# GTM_MCU.net
KiCad netlist of a schematic drawn in Altium Designer
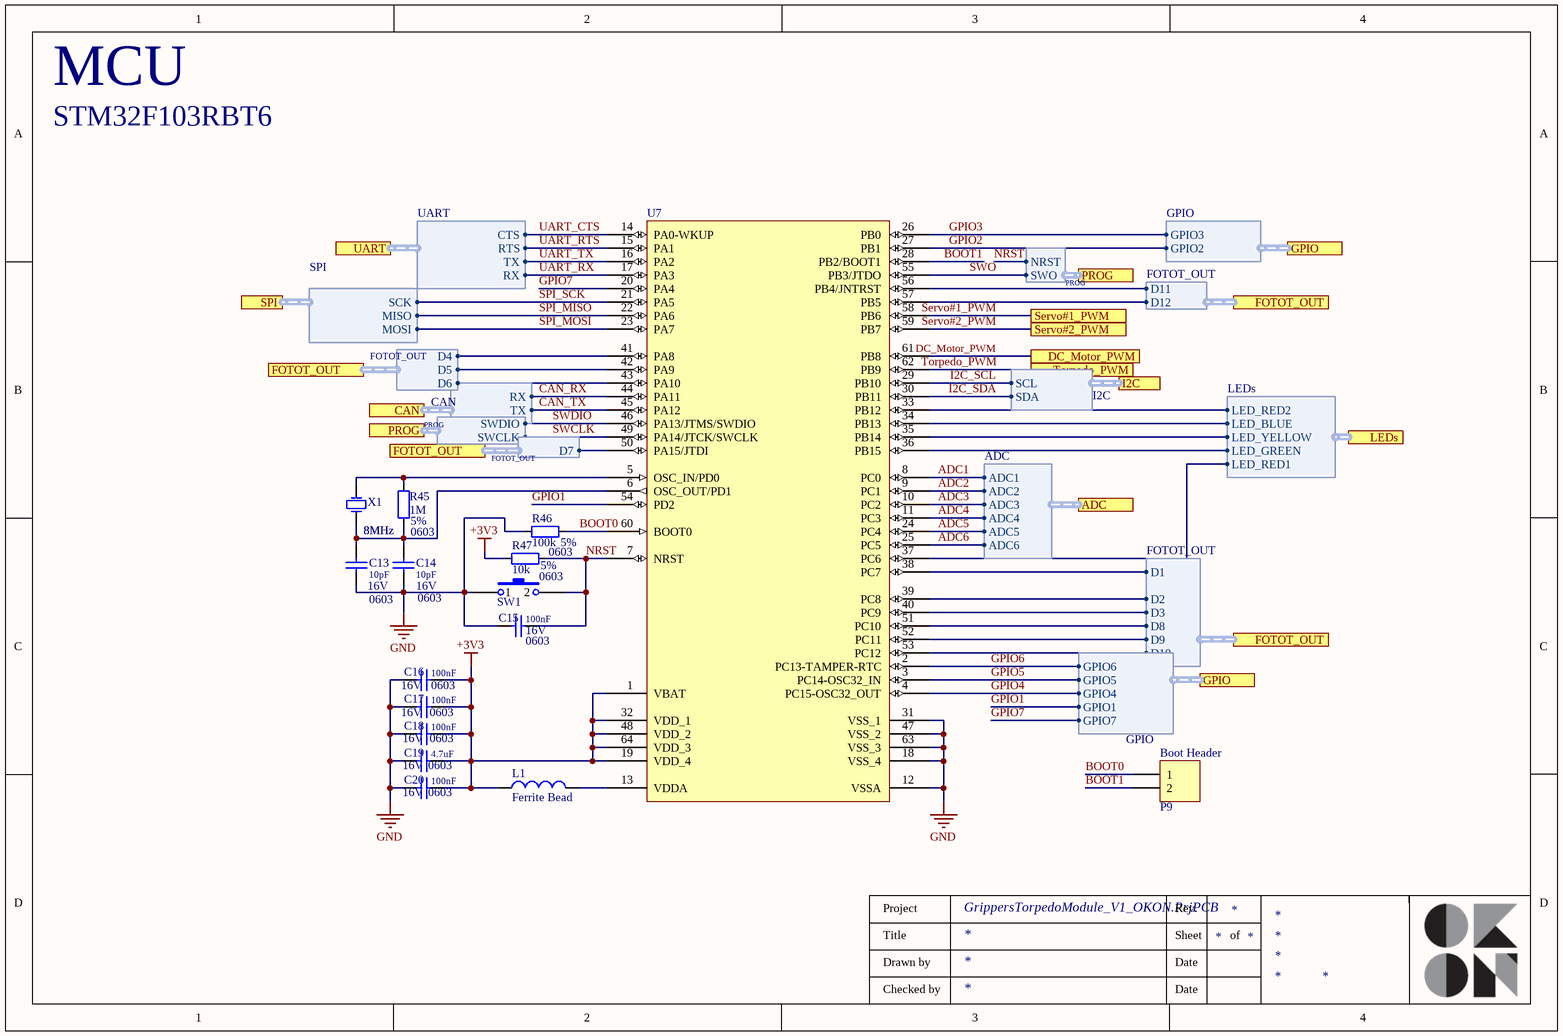
[diagram p0: GTM_MCU.SchDoc]

(export (version "E")
  (design (tool "Eeschema 10.0.6"))
  (components
    (comp (ref "C13")
      (value "10pF")
      (footprint "0603_CAP")
      (description "Ceramic capacitor")
      (fields (field (name "CAPACITY") "16V") (field (name "PACKAGE") "0603") (field (name "Comment") "Cap"))
      (libsource (lib "Library_Altium_KNR") (part "Cap"))
    )
    (comp (ref "C14")
      (value "10pF")
      (footprint "0603_CAP")
      (description "Ceramic capacitor")
      (fields (field (name "CAPACITY") "16V") (field (name "PACKAGE") "0603") (field (name "Comment") "Cap"))
      (libsource (lib "Library_Altium_KNR") (part "Cap"))
    )
    (comp (ref "C15")
      (value "100nF")
      (footprint "0603_CAP")
      (description "Ceramic capacitor")
      (fields (field (name "CAPACITY") "16V") (field (name "PACKAGE") "0603") (field (name "Comment") "Cap"))
      (libsource (lib "Library_Altium_KNR") (part "Cap"))
    )
    (comp (ref "C16")
      (value "100nF")
      (footprint "0603_CAP")
      (description "Ceramic capacitor")
      (fields (field (name "CAPACITY") "16V") (field (name "PACKAGE") "0603") (field (name "Comment") "Cap"))
      (libsource (lib "Library_Altium_KNR") (part "Cap"))
    )
    (comp (ref "C17")
      (value "100nF")
      (footprint "0603_CAP")
      (description "Ceramic capacitor")
      (fields (field (name "CAPACITY") "16V") (field (name "PACKAGE") "0603") (field (name "Comment") "Cap"))
      (libsource (lib "Library_Altium_KNR") (part "Cap"))
    )
    (comp (ref "C18")
      (value "100nF")
      (footprint "0603_CAP")
      (description "Ceramic capacitor")
      (fields (field (name "CAPACITY") "16V") (field (name "PACKAGE") "0603") (field (name "Comment") "Cap"))
      (libsource (lib "Library_Altium_KNR") (part "Cap"))
    )
    (comp (ref "C19")
      (value "4.7uF")
      (footprint "0603_CAP")
      (description "Ceramic capacitor")
      (fields (field (name "CAPACITY") "16V") (field (name "PACKAGE") "0603") (field (name "Comment") "Cap"))
      (libsource (lib "Library_Altium_KNR") (part "Cap"))
    )
    (comp (ref "C20")
      (value "100nF")
      (footprint "0603_CAP")
      (description "Ceramic capacitor")
      (fields (field (name "CAPACITY") "16V") (field (name "PACKAGE") "0603") (field (name "Comment") "Cap"))
      (libsource (lib "Library_Altium_KNR") (part "Cap"))
    )
    (comp (ref "L1")
      (value "Ferrite Bead")
      (footprint "DO5040")
      (description "DO5040H-103")
      (fields (field (name "PUBLISHER") "Altium Limited"))
      (libsource (lib "Library_Altium_KNR") (part "Inductor"))
    )
    (comp (ref "P9")
      (value "Boot Header")
      (footprint "HDR1X2")
      (description "Header, 2-Pin")
      (fields (field (name "PUBLISHER") "Altium Limited"))
      (libsource (lib "Library_Altium_KNR") (part "HDR1X2"))
    )
    (comp (ref "R45")
      (value "1M")
      (footprint "0603")
      (description "Resistior")
      (fields (field (name "TOLERANCE") "5%") (field (name "PACKAGE") "0603"))
      (libsource (lib "") (part "RES_1"))
    )
    (comp (ref "R46")
      (value "100k")
      (footprint "0603")
      (description "Resistior")
      (fields (field (name "TOLERANCE") "5%") (field (name "PACKAGE") "0603"))
      (libsource (lib "Library_Altium_KNR") (part "RES"))
    )
    (comp (ref "R47")
      (value "10k")
      (footprint "0603")
      (description "Resistior")
      (fields (field (name "TOLERANCE") "5%") (field (name "PACKAGE") "0603"))
      (libsource (lib "Library_Altium_KNR") (part "RES"))
    )
    (comp (ref "SW1")
      (value "Micro_Switch")
      (footprint "Tact 34N-F")
      (description "Switch")
      (fields (field (name "PUBLISHER") "Altium Limited"))
      (libsource (lib "Library_Altium_KNR") (part "Micro_Switch"))
    )
    (comp (ref "U7")
      (value "STM32F103RBT6")
      (footprint "LQFP64_L")
      (description "STM32 ARM-based 32-bit")
      (fields (field (name "PUBLISHER") "Altium Limited"))
      (libsource (lib "Library_Altium_KNR") (part "STM32F103RBT6"))
    )
    (comp (ref "X1")
      (value "8MHz")
      (footprint "HC49/4H_SMX")
      (description "Oscillator")
      (fields (field (name "ALTIUM_VALUE") "8MHz"))
      (libsource (lib "Library_Altium_KNR") (part "XTAL"))
    )
  )
  (nets
    (net (code "10") (name "+3V3") (class "Default")
      (node (ref "C16") (pin "2") (pinfunction "2_2") (pintype "passive"))
      (node (ref "C17") (pin "2") (pinfunction "2_2") (pintype "passive"))
      (node (ref "C18") (pin "2") (pinfunction "2_2") (pintype "passive"))
      (node (ref "C19") (pin "2") (pinfunction "2_2") (pintype "passive"))
      (node (ref "C20") (pin "2") (pinfunction "2_2") (pintype "passive"))
      (node (ref "L1") (pin "1") (pinfunction "1_1") (pintype "passive"))
      (node (ref "R47") (pin "2") (pinfunction "2_2") (pintype "passive"))
      (node (ref "U7") (pin "1") (pinfunction "VBAT_1") (pintype "power_in"))
      (node (ref "U7") (pin "19") (pinfunction "VDD_4_19") (pintype "power_in"))
      (node (ref "U7") (pin "32") (pinfunction "VDD_1_32") (pintype "power_in"))
      (node (ref "U7") (pin "48") (pinfunction "VDD_2_48") (pintype "power_in"))
      (node (ref "U7") (pin "64") (pinfunction "VDD_3_64") (pintype "power_in"))
    )
    (net (code "11") (name "/ADC1") (class "Default")
      (node (ref "U7") (pin "8") (pinfunction "PC0_8") (pintype "bidirectional"))
    )
    (net (code "12") (name "/ADC2") (class "Default")
      (node (ref "U7") (pin "9") (pinfunction "PC1_9") (pintype "bidirectional"))
    )
    (net (code "13") (name "/ADC3") (class "Default")
      (node (ref "U7") (pin "10") (pinfunction "PC2_10") (pintype "bidirectional"))
    )
    (net (code "14") (name "/ADC4") (class "Default")
      (node (ref "U7") (pin "11") (pinfunction "PC3_11") (pintype "bidirectional"))
    )
    (net (code "15") (name "/ADC5") (class "Default")
      (node (ref "U7") (pin "24") (pinfunction "PC4_24") (pintype "bidirectional"))
    )
    (net (code "16") (name "/ADC6") (class "Default")
      (node (ref "U7") (pin "25") (pinfunction "PC5_25") (pintype "bidirectional"))
    )
    (net (code "17") (name "/BOOT0") (class "Default")
      (node (ref "P9") (pin "1") (pinfunction "1_1") (pintype "passive"))
      (node (ref "R46") (pin "1") (pinfunction "1_1") (pintype "passive"))
      (node (ref "U7") (pin "60") (pinfunction "BOOT0_60") (pintype "input"))
    )
    (net (code "18") (name "/BOOT1") (class "Default")
      (node (ref "P9") (pin "2") (pinfunction "2_2") (pintype "passive"))
      (node (ref "U7") (pin "28") (pinfunction "PB2/BOOT1_28") (pintype "bidirectional"))
    )
    (net (code "19") (name "/CAN_RX") (class "Default")
      (node (ref "U7") (pin "44") (pinfunction "PA11_44") (pintype "bidirectional"))
    )
    (net (code "20") (name "/CAN_TX") (class "Default")
      (node (ref "U7") (pin "45") (pinfunction "PA12_45") (pintype "bidirectional"))
    )
    (net (code "21") (name "/D1") (class "Default")
      (node (ref "U7") (pin "38") (pinfunction "PC7_38") (pintype "bidirectional"))
    )
    (net (code "22") (name "/D2") (class "Default")
      (node (ref "U7") (pin "39") (pinfunction "PC8_39") (pintype "bidirectional"))
    )
    (net (code "23") (name "/D3") (class "Default")
      (node (ref "U7") (pin "40") (pinfunction "PC9_40") (pintype "bidirectional"))
    )
    (net (code "24") (name "/D4") (class "Default")
      (node (ref "U7") (pin "41") (pinfunction "PA8_41") (pintype "bidirectional"))
    )
    (net (code "25") (name "/D5") (class "Default")
      (node (ref "U7") (pin "42") (pinfunction "PA9_42") (pintype "bidirectional"))
    )
    (net (code "26") (name "/D6") (class "Default")
      (node (ref "U7") (pin "43") (pinfunction "PA10_43") (pintype "bidirectional"))
    )
    (net (code "27") (name "/D7") (class "Default")
      (node (ref "U7") (pin "50") (pinfunction "PA15/JTDI_50") (pintype "bidirectional"))
    )
    (net (code "28") (name "/D8") (class "Default")
      (node (ref "U7") (pin "51") (pinfunction "PC10_51") (pintype "bidirectional"))
    )
    (net (code "29") (name "/D9") (class "Default")
      (node (ref "U7") (pin "52") (pinfunction "PC11_52") (pintype "bidirectional"))
    )
    (net (code "30") (name "/D10") (class "Default")
      (node (ref "U7") (pin "53") (pinfunction "PC12_53") (pintype "bidirectional"))
    )
    (net (code "31") (name "/D11") (class "Default")
      (node (ref "U7") (pin "56") (pinfunction "PB4/JNTRST_56") (pintype "bidirectional"))
    )
    (net (code "32") (name "/D12") (class "Default")
      (node (ref "U7") (pin "57") (pinfunction "PB5_57") (pintype "bidirectional"))
    )
    (net (code "33") (name "/DC_Motor_PWM") (class "Default")
      (node (ref "U7") (pin "61") (pinfunction "PB8_61") (pintype "bidirectional"))
    )
    (net (code "34") (name "/GPIO1") (class "Default")
      (node (ref "U7") (pin "54") (pinfunction "PD2_54") (pintype "bidirectional"))
    )
    (net (code "35") (name "/GPIO2") (class "Default")
      (node (ref "U7") (pin "27") (pinfunction "PB1_27") (pintype "bidirectional"))
    )
    (net (code "36") (name "/GPIO3") (class "Default")
      (node (ref "U7") (pin "26") (pinfunction "PB0_26") (pintype "bidirectional"))
    )
    (net (code "37") (name "/GPIO4") (class "Default")
      (node (ref "U7") (pin "4") (pinfunction "PC15-OSC32_OUT_4") (pintype "bidirectional"))
    )
    (net (code "38") (name "/GPIO5") (class "Default")
      (node (ref "U7") (pin "3") (pinfunction "PC14-OSC32_IN_3") (pintype "bidirectional"))
    )
    (net (code "39") (name "/GPIO6") (class "Default")
      (node (ref "U7") (pin "2") (pinfunction "PC13-TAMPER-RTC_2") (pintype "bidirectional"))
    )
    (net (code "40") (name "/GPIO7") (class "Default")
      (node (ref "U7") (pin "20") (pinfunction "PA4_20") (pintype "bidirectional"))
    )
    (net (code "41") (name "/I2C_SCL") (class "Default")
      (node (ref "U7") (pin "29") (pinfunction "PB10_29") (pintype "bidirectional"))
    )
    (net (code "42") (name "/I2C_SDA") (class "Default")
      (node (ref "U7") (pin "30") (pinfunction "PB11_30") (pintype "bidirectional"))
    )
    (net (code "43") (name "/LED_BLUE") (class "Default")
      (node (ref "U7") (pin "34") (pinfunction "PB13_34") (pintype "bidirectional"))
    )
    (net (code "44") (name "/LED_GREEN") (class "Default")
      (node (ref "U7") (pin "36") (pinfunction "PB15_36") (pintype "bidirectional"))
    )
    (net (code "45") (name "/LED_RED1") (class "Default")
      (node (ref "U7") (pin "37") (pinfunction "PC6_37") (pintype "bidirectional"))
    )
    (net (code "46") (name "/LED_RED2") (class "Default")
      (node (ref "U7") (pin "33") (pinfunction "PB12_33") (pintype "bidirectional"))
    )
    (net (code "47") (name "/LED_YELLOW") (class "Default")
      (node (ref "U7") (pin "35") (pinfunction "PB14_35") (pintype "bidirectional"))
    )
    (net (code "48") (name "/NRST") (class "Default")
      (node (ref "C15") (pin "2") (pinfunction "2_2") (pintype "passive"))
      (node (ref "R47") (pin "1") (pinfunction "1_1") (pintype "passive"))
      (node (ref "SW1") (pin "2") (pinfunction "2_2") (pintype "passive"))
      (node (ref "U7") (pin "7") (pinfunction "NRST_7") (pintype "bidirectional"))
    )
    (net (code "49") (name "/SPI_MISO") (class "Default")
      (node (ref "U7") (pin "22") (pinfunction "PA6_22") (pintype "bidirectional"))
    )
    (net (code "50") (name "/SPI_MOSI") (class "Default")
      (node (ref "U7") (pin "23") (pinfunction "PA7_23") (pintype "bidirectional"))
    )
    (net (code "51") (name "/SPI_SCK") (class "Default")
      (node (ref "U7") (pin "21") (pinfunction "PA5_21") (pintype "bidirectional"))
    )
    (net (code "52") (name "/SWDIO") (class "Default")
      (node (ref "U7") (pin "46") (pinfunction "PA13/JTMS/SWDIO_46") (pintype "bidirectional"))
    )
    (net (code "53") (name "/SWO") (class "Default")
      (node (ref "U7") (pin "55") (pinfunction "PB3/JTDO_55") (pintype "bidirectional"))
    )
    (net (code "54") (name "/Servo#1_PWM") (class "Default")
      (node (ref "U7") (pin "58") (pinfunction "PB6_58") (pintype "bidirectional"))
    )
    (net (code "55") (name "/Servo#2_PWM") (class "Default")
      (node (ref "U7") (pin "59") (pinfunction "PB7_59") (pintype "bidirectional"))
    )
    (net (code "56") (name "/Torpedo_PWM") (class "Default")
      (node (ref "U7") (pin "62") (pinfunction "PB9_62") (pintype "bidirectional"))
    )
    (net (code "57") (name "/UART_CTS") (class "Default")
      (node (ref "U7") (pin "14") (pinfunction "PA0-WKUP_14") (pintype "bidirectional"))
    )
    (net (code "58") (name "/UART_RTS") (class "Default")
      (node (ref "U7") (pin "15") (pinfunction "PA1_15") (pintype "bidirectional"))
    )
    (net (code "59") (name "/UART_RX") (class "Default")
      (node (ref "U7") (pin "17") (pinfunction "PA3_17") (pintype "bidirectional"))
    )
    (net (code "60") (name "/UART_TX") (class "Default")
      (node (ref "U7") (pin "16") (pinfunction "PA2_16") (pintype "bidirectional"))
    )
    (net (code "63") (name "/{FOTOT_OUT}") (class "Default")
      (node (ref "U7") (pin "49") (pinfunction "PA14/JTCK/SWCLK_49") (pintype "bidirectional"))
    )
    (net (code "70") (name "GND") (class "Default")
      (node (ref "C13") (pin "1") (pinfunction "1_1") (pintype "passive"))
      (node (ref "C14") (pin "1") (pinfunction "1_1") (pintype "passive"))
      (node (ref "C15") (pin "1") (pinfunction "1_1") (pintype "passive"))
      (node (ref "C16") (pin "1") (pinfunction "1_1") (pintype "passive"))
      (node (ref "C17") (pin "1") (pinfunction "1_1") (pintype "passive"))
      (node (ref "C18") (pin "1") (pinfunction "1_1") (pintype "passive"))
      (node (ref "C19") (pin "1") (pinfunction "1_1") (pintype "passive"))
      (node (ref "C20") (pin "1") (pinfunction "1_1") (pintype "passive"))
      (node (ref "R46") (pin "2") (pinfunction "2_2") (pintype "passive"))
      (node (ref "SW1") (pin "1") (pinfunction "1_1") (pintype "passive"))
      (node (ref "U7") (pin "12") (pinfunction "VSSA_12") (pintype "power_in"))
      (node (ref "U7") (pin "18") (pinfunction "VSS_4_18") (pintype "power_in"))
      (node (ref "U7") (pin "31") (pinfunction "VSS_1_31") (pintype "power_in"))
      (node (ref "U7") (pin "47") (pinfunction "VSS_2_47") (pintype "power_in"))
      (node (ref "U7") (pin "63") (pinfunction "VSS_3_63") (pintype "power_in"))
    )
    (net (code "71") (name "Net-(U7-OSC_IN{slash}PD0)") (class "Default")
      (node (ref "R45") (pin "2") (pinfunction "2_2") (pintype "passive"))
      (node (ref "U7") (pin "5") (pinfunction "OSC_IN/PD0_5") (pintype "input"))
      (node (ref "X1") (pin "2") (pinfunction "OSC2_2") (pintype "passive"))
    )
    (net (code "72") (name "Net-(U7-OSC_OUT{slash}PD1)") (class "Default")
      (node (ref "C13") (pin "2") (pinfunction "2_2") (pintype "passive"))
      (node (ref "C14") (pin "2") (pinfunction "2_2") (pintype "passive"))
      (node (ref "R45") (pin "1") (pinfunction "1_1") (pintype "passive"))
      (node (ref "U7") (pin "6") (pinfunction "OSC_OUT/PD1_6") (pintype "output"))
      (node (ref "X1") (pin "1") (pinfunction "OSC1_1") (pintype "passive"))
    )
    (net (code "73") (name "Net-(U7-VDDA)") (class "Default")
      (node (ref "L1") (pin "2") (pinfunction "2_2") (pintype "passive"))
      (node (ref "U7") (pin "13") (pinfunction "VDDA_13") (pintype "power_in"))
    )
  )
)
